# Encoder.net
KiCad netlist of a schematic drawn in Altium Designer
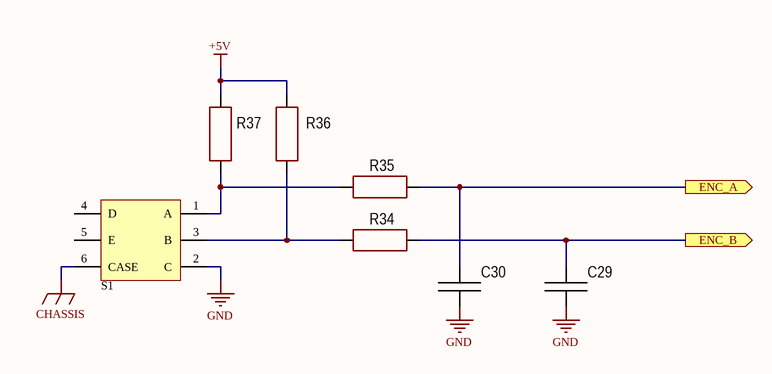
[diagram p0: Encoder.SchDoc]

(export (version "E")
  (design (tool "Eeschema 10.0.6"))
  (components
    (comp (ref "C29")
      (value "~")
      (footprint "StandardCase:CAP: 1206")
      (fields
        (field (name "MANUFACTURER") "Yageo")
        (field (name "PARTNUMBER") "CC1206KRX7R9BB104")
        (field (name "VALUEMANUFACTURERPARTNUMBER") "Ceramic capacitor, 10nF, 1206")
      )
      (libsource (lib "Capacitor") (part "Ceramic_1206"))
    )
    (comp (ref "C30")
      (value "~")
      (footprint "StandardCase:CAP: 1206")
      (fields
        (field (name "MANUFACTURER") "Yageo")
        (field (name "PARTNUMBER") "CC1206KRX7R9BB104")
        (field (name "VALUEMANUFACTURERPARTNUMBER") "Ceramic capacitor, 10nF, 1206")
      )
      (libsource (lib "Capacitor") (part "Ceramic_1206"))
    )
    (comp (ref "R34")
      (value "~")
      (footprint "StandardCase:RES: 1206")
      (fields
        (field (name "MANUFACTURER") "Yageo")
        (field (name "PARTNUMBER") "RC1206JR-07100RL")
        (field (name "VALUEMANUFACTURERPARTNUMBER") "Resistor, 10K, 1206")
      )
      (libsource (lib "Resistor") (part "Resistor_1206"))
    )
    (comp (ref "R35")
      (value "~")
      (footprint "StandardCase:RES: 1206")
      (fields
        (field (name "MANUFACTURER") "Yageo")
        (field (name "PARTNUMBER") "RC1206JR-07100RL")
        (field (name "VALUEMANUFACTURERPARTNUMBER") "Resistor, 10K, 1206")
      )
      (libsource (lib "") (part "Resistor_1206_1"))
    )
    (comp (ref "R36")
      (value "~")
      (footprint "StandardCase:RES: 1206")
      (fields
        (field (name "MANUFACTURER") "Yageo")
        (field (name "PARTNUMBER") "RC1206JR-07100RL")
        (field (name "VALUEMANUFACTURERPARTNUMBER") "Resistor, 1K, 1206")
      )
      (libsource (lib "") (part "Resistor_1206_2"))
    )
    (comp (ref "R37")
      (value "~")
      (footprint "StandardCase:RES: 1206")
      (fields
        (field (name "MANUFACTURER") "Yageo")
        (field (name "PARTNUMBER") "RC1206JR-07100RL")
        (field (name "VALUEMANUFACTURERPARTNUMBER") "Resistor, 1K, 1206")
      )
      (libsource (lib "") (part "Resistor_1206_2"))
    )
    (comp (ref "S1")
      (value "~")
      (footprint "FP_lib_PCB:PEC11L")
      (fields (field (name "VALUEMANUFACTURERPARTNUMBER") "PEC11L"))
      (libsource (lib "FP_lib_SCH") (part "PEC11L"))
    )
  )
  (nets
    (net (code "1") (name "+5V") (class "Default")
      (node (ref "R36") (pin "2") (pinfunction "2_2") (pintype "passive"))
      (node (ref "R37") (pin "2") (pinfunction "2_2") (pintype "passive"))
    )
    (net (code "2") (name "/ENC_A") (class "Default")
      (node (ref "C30") (pin "2") (pinfunction "2_2") (pintype "power_in"))
      (node (ref "R35") (pin "1") (pinfunction "1_1") (pintype "passive"))
    )
    (net (code "3") (name "/ENC_B") (class "Default")
      (node (ref "C29") (pin "2") (pinfunction "2_2") (pintype "power_in"))
      (node (ref "R34") (pin "2") (pinfunction "2_2") (pintype "passive"))
    )
    (net (code "4") (name "CHASSIS") (class "Default")
      (node (ref "S1") (pin "6") (pinfunction "CASE_6") (pintype "passive"))
    )
    (net (code "5") (name "GND") (class "Default")
      (node (ref "C29") (pin "1") (pinfunction "1_1") (pintype "power_in"))
      (node (ref "C30") (pin "1") (pinfunction "1_1") (pintype "power_in"))
      (node (ref "S1") (pin "2") (pinfunction "C_2") (pintype "passive"))
    )
    (net (code "6") (name "Net-(S1-A)") (class "Default")
      (node (ref "R35") (pin "2") (pinfunction "2_2") (pintype "passive"))
      (node (ref "R37") (pin "1") (pinfunction "1_1") (pintype "passive"))
      (node (ref "S1") (pin "1") (pinfunction "A_1") (pintype "passive"))
    )
    (net (code "7") (name "Net-(S1-B)") (class "Default")
      (node (ref "R34") (pin "1") (pinfunction "1_1") (pintype "passive"))
      (node (ref "R36") (pin "1") (pinfunction "1_1") (pintype "passive"))
      (node (ref "S1") (pin "3") (pinfunction "B_3") (pintype "passive"))
    )
    (net (code "8") (name "unconnected-(S1-D-Pad4)") (class "Default")
      (node (ref "S1") (pin "4") (pinfunction "D_4") (pintype "passive"))
    )
    (net (code "9") (name "unconnected-(S1-E-Pad5)") (class "Default")
      (node (ref "S1") (pin "5") (pinfunction "E_5") (pintype "passive"))
    )
  )
)
